# Power.net
KiCad netlist of a schematic drawn in Altium Designer
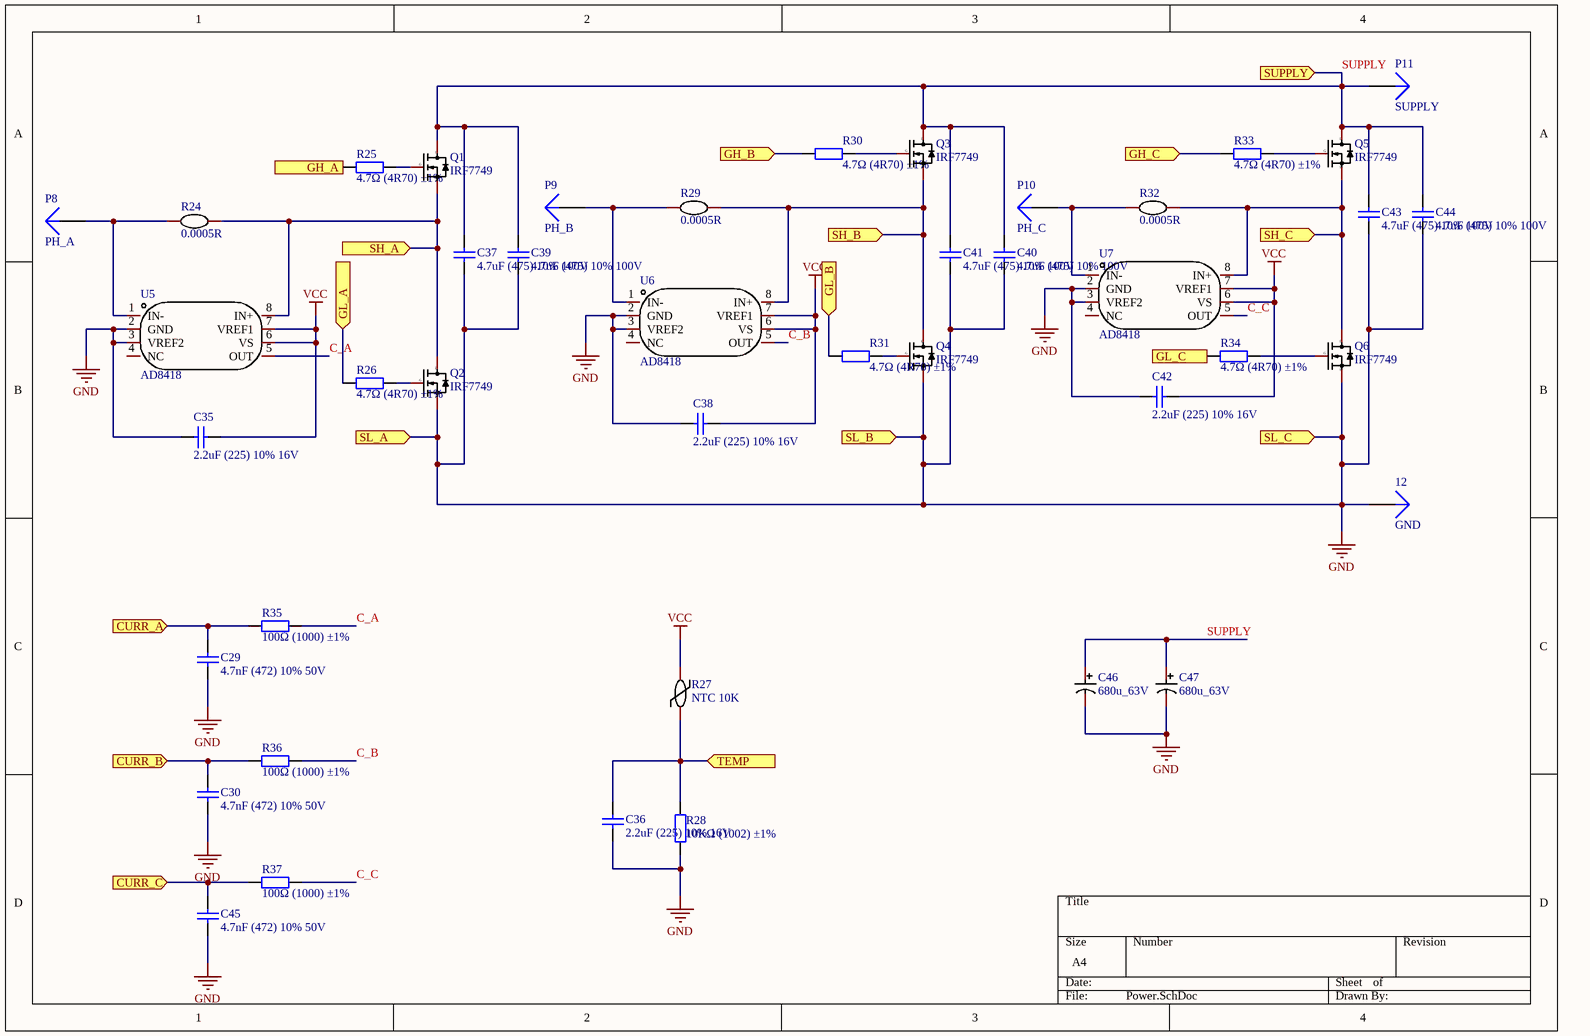
[diagram p0: Power.SchDoc]

(export (version "E")
  (design (tool "Eeschema 10.0.6"))
  (components
    (comp (ref "12")
      (value "GND")
      (footprint "Power PAD6x6")
      (description "Plug")
      (fields (field (name "PUBLISHER") "Altium Limited"))
      (libsource (lib "Miscellaneous Connectors") (part "Plug"))
    )
    (comp (ref "C29")
      (value "4.7nF (472) 10% 50V")
      (footprint "0603_C")
      (description "贴片电容")
      (libsource (lib "Miscellaneous Devices LC") (part "0603 4.7nF (472) 10% 50V"))
    )
    (comp (ref "C30")
      (value "4.7nF (472) 10% 50V")
      (footprint "0603_C")
      (description "贴片电容")
      (libsource (lib "Miscellaneous Devices LC") (part "0603 4.7nF (472) 10% 50V"))
    )
    (comp (ref "C35")
      (value "2.2uF (225) 10% 16V")
      (footprint "0603_C")
      (description "贴片电容")
      (libsource (lib "Miscellaneous Devices LC") (part "0603 2.2uF (225) 10% 16V"))
    )
    (comp (ref "C36")
      (value "2.2uF (225) 10% 16V")
      (footprint "0603_C")
      (description "贴片电容")
      (libsource (lib "Miscellaneous Devices LC") (part "0603 2.2uF (225) 10% 16V"))
    )
    (comp (ref "C37")
      (value "4.7uF (475) 10% 100V")
      (footprint "1210_C")
      (description "贴片电容")
      (libsource (lib "Miscellaneous Devices LC") (part "0603 4.7uF (475) 10% 16V"))
    )
    (comp (ref "C38")
      (value "2.2uF (225) 10% 16V")
      (footprint "0603_C")
      (description "贴片电容")
      (libsource (lib "Miscellaneous Devices LC") (part "0603 2.2uF (225) 10% 16V"))
    )
    (comp (ref "C39")
      (value "4.7uF (475) 10% 100V")
      (footprint "1210_C")
      (description "贴片电容")
      (libsource (lib "Miscellaneous Devices LC") (part "0603 4.7uF (475) 10% 16V"))
    )
    (comp (ref "C40")
      (value "4.7uF (475) 10% 100V")
      (footprint "1210_C")
      (description "贴片电容")
      (libsource (lib "Miscellaneous Devices LC") (part "0603 4.7uF (475) 10% 16V"))
    )
    (comp (ref "C41")
      (value "4.7uF (475) 10% 100V")
      (footprint "1210_C")
      (description "贴片电容")
      (libsource (lib "Miscellaneous Devices LC") (part "0603 4.7uF (475) 10% 16V"))
    )
    (comp (ref "C42")
      (value "2.2uF (225) 10% 16V")
      (footprint "0603_C")
      (description "贴片电容")
      (libsource (lib "Miscellaneous Devices LC") (part "0603 2.2uF (225) 10% 16V"))
    )
    (comp (ref "C43")
      (value "4.7uF (475) 10% 100V")
      (footprint "1210_C")
      (description "贴片电容")
      (libsource (lib "Miscellaneous Devices LC") (part "0603 4.7uF (475) 10% 16V"))
    )
    (comp (ref "C44")
      (value "4.7uF (475) 10% 100V")
      (footprint "1210_C")
      (description "贴片电容")
      (libsource (lib "Miscellaneous Devices LC") (part "0603 4.7uF (475) 10% 16V"))
    )
    (comp (ref "C45")
      (value "4.7nF (472) 10% 50V")
      (footprint "0603_C")
      (description "贴片电容")
      (libsource (lib "Miscellaneous Devices LC") (part "0603 4.7nF (472) 10% 50V"))
    )
    (comp (ref "C46") (value "680u_63V") (footprint "680u_63V") (libsource (lib "VESC_6") (part "680u_63V")))
    (comp (ref "C47") (value "680u_63V") (footprint "680u_63V") (libsource (lib "VESC_6") (part "680u_63V")))
    (comp (ref "P8")
      (value "PH_A")
      (footprint "POWER PAD")
      (description "Plug")
      (fields (field (name "PUBLISHER") "Altium Limited"))
      (libsource (lib "Miscellaneous Connectors") (part "Plug"))
    )
    (comp (ref "P9")
      (value "PH_B")
      (footprint "POWER PAD")
      (description "Plug")
      (fields (field (name "PUBLISHER") "Altium Limited"))
      (libsource (lib "Miscellaneous Connectors") (part "Plug"))
    )
    (comp (ref "P10")
      (value "PH_C")
      (footprint "POWER PAD")
      (description "Plug")
      (fields (field (name "PUBLISHER") "Altium Limited"))
      (libsource (lib "Miscellaneous Connectors") (part "Plug"))
    )
    (comp (ref "P11")
      (value "SUPPLY")
      (footprint "Power PAD6x6")
      (description "Plug")
      (fields (field (name "PUBLISHER") "Altium Limited"))
      (libsource (lib "Miscellaneous Connectors") (part "Plug"))
    )
    (comp (ref "Q1") (value "IRF7749") (footprint "IRF7749") (libsource (lib "VESC_6") (part "IRF7749")))
    (comp (ref "Q2") (value "IRF7749") (footprint "IRF7749") (libsource (lib "VESC_6") (part "IRF7749")))
    (comp (ref "Q3") (value "IRF7749") (footprint "IRF7749") (libsource (lib "VESC_6") (part "IRF7749")))
    (comp (ref "Q4") (value "IRF7749") (footprint "IRF7749") (libsource (lib "VESC_6") (part "IRF7749")))
    (comp (ref "Q5") (value "IRF7749") (footprint "IRF7749") (libsource (lib "VESC_6") (part "IRF7749")))
    (comp (ref "Q6") (value "IRF7749") (footprint "IRF7749") (libsource (lib "VESC_6") (part "IRF7749")))
    (comp (ref "R24") (value "0.0005R") (footprint "0.0005R") (libsource (lib "VESC_6") (part "0.0005R")))
    (comp (ref "R25")
      (value "4.7Ω (4R70) ±1%")
      (footprint "0603_R")
      (description "贴片电阻")
      (libsource (lib "Miscellaneous Devices LC") (part "0603 4.7Ω (4R70) 1%"))
    )
    (comp (ref "R26")
      (value "4.7Ω (4R70) ±1%")
      (footprint "0603_R")
      (description "贴片电阻")
      (libsource (lib "Miscellaneous Devices LC") (part "0603 4.7Ω (4R70) 1%"))
    )
    (comp (ref "R27") (value "NTC 10K") (footprint "NTC 10K") (libsource (lib "VESC_6") (part "NTC 10K")))
    (comp (ref "R28")
      (value "10KΩ (1002) ±1%")
      (footprint "0603_R")
      (description "贴片电阻")
      (libsource (lib "Miscellaneous Devices LC") (part "0603 10KΩ (1002) 1%"))
    )
    (comp (ref "R29") (value "0.0005R") (footprint "0.0005R") (libsource (lib "VESC_6") (part "0.0005R")))
    (comp (ref "R30")
      (value "4.7Ω (4R70) ±1%")
      (footprint "0603_R")
      (description "贴片电阻")
      (libsource (lib "Miscellaneous Devices LC") (part "0603 4.7Ω (4R70) 1%"))
    )
    (comp (ref "R31")
      (value "4.7Ω (4R70) ±1%")
      (footprint "0603_R")
      (description "贴片电阻")
      (libsource (lib "Miscellaneous Devices LC") (part "0603 4.7Ω (4R70) 1%"))
    )
    (comp (ref "R32") (value "0.0005R") (footprint "0.0005R") (libsource (lib "VESC_6") (part "0.0005R")))
    (comp (ref "R33")
      (value "4.7Ω (4R70) ±1%")
      (footprint "0603_R")
      (description "贴片电阻")
      (libsource (lib "Miscellaneous Devices LC") (part "0603 4.7Ω (4R70) 1%"))
    )
    (comp (ref "R34")
      (value "4.7Ω (4R70) ±1%")
      (footprint "0603_R")
      (description "贴片电阻")
      (libsource (lib "Miscellaneous Devices LC") (part "0603 4.7Ω (4R70) 1%"))
    )
    (comp (ref "R35")
      (value "100Ω (1000) ±1%")
      (footprint "0603_R")
      (description "贴片电阻")
      (libsource (lib "Miscellaneous Devices LC") (part "0603 100Ω (1000) 1%"))
    )
    (comp (ref "R36")
      (value "100Ω (1000) ±1%")
      (footprint "0603_R")
      (description "贴片电阻")
      (libsource (lib "Miscellaneous Devices LC") (part "0603 100Ω (1000) 1%"))
    )
    (comp (ref "R37")
      (value "100Ω (1000) ±1%")
      (footprint "0603_R")
      (description "贴片电阻")
      (libsource (lib "Miscellaneous Devices LC") (part "0603 100Ω (1000) 1%"))
    )
    (comp (ref "U5") (value "AD8418") (footprint "AD8418") (libsource (lib "VESC_6") (part "AD8418")))
    (comp (ref "U6") (value "AD8418") (footprint "AD8418") (libsource (lib "VESC_6") (part "AD8418")))
    (comp (ref "U7") (value "AD8418") (footprint "AD8418") (libsource (lib "VESC_6") (part "AD8418")))
  )
  (nets
    (net (code "1") (name "/CURR_A") (class "Default")
      (node (ref "C29") (pin "2") (pinfunction "2_2") (pintype "passive"))
      (node (ref "R35") (pin "1") (pinfunction "1_1") (pintype "passive"))
    )
    (net (code "2") (name "/CURR_B") (class "Default")
      (node (ref "C30") (pin "2") (pinfunction "2_2") (pintype "passive"))
      (node (ref "R36") (pin "1") (pinfunction "1_1") (pintype "passive"))
    )
    (net (code "3") (name "/CURR_C") (class "Default")
      (node (ref "C45") (pin "2") (pinfunction "2_2") (pintype "passive"))
      (node (ref "R37") (pin "1") (pinfunction "1_1") (pintype "passive"))
    )
    (net (code "4") (name "/C_A") (class "Default")
      (node (ref "R35") (pin "2") (pinfunction "2_2") (pintype "passive"))
      (node (ref "U5") (pin "5") (pinfunction "OUT_5") (pintype "passive"))
    )
    (net (code "5") (name "/C_B") (class "Default")
      (node (ref "R36") (pin "2") (pinfunction "2_2") (pintype "passive"))
      (node (ref "U6") (pin "5") (pinfunction "OUT_5") (pintype "passive"))
    )
    (net (code "6") (name "/C_C") (class "Default")
      (node (ref "R37") (pin "2") (pinfunction "2_2") (pintype "passive"))
      (node (ref "U7") (pin "5") (pinfunction "OUT_5") (pintype "passive"))
    )
    (net (code "7") (name "/GH_A") (class "Default")
      (node (ref "R25") (pin "1") (pinfunction "1_1") (pintype "passive"))
    )
    (net (code "8") (name "/GH_B") (class "Default")
      (node (ref "R30") (pin "1") (pinfunction "1_1") (pintype "passive"))
    )
    (net (code "9") (name "/GH_C") (class "Default")
      (node (ref "R33") (pin "1") (pinfunction "1_1") (pintype "passive"))
    )
    (net (code "10") (name "/GL_A") (class "Default")
      (node (ref "R26") (pin "1") (pinfunction "1_1") (pintype "passive"))
    )
    (net (code "11") (name "/GL_B") (class "Default")
      (node (ref "R31") (pin "1") (pinfunction "1_1") (pintype "passive"))
    )
    (net (code "12") (name "/GL_C") (class "Default")
      (node (ref "R34") (pin "1") (pinfunction "1_1") (pintype "passive"))
    )
    (net (code "13") (name "/SH_A") (class "Default")
      (node (ref "Q1") (pin "3") (pinfunction "S_3") (pintype "passive"))
      (node (ref "Q2") (pin "4") (pinfunction "D_4") (pintype "passive"))
      (node (ref "R24") (pin "2") (pinfunction "2_2") (pintype "passive"))
      (node (ref "U5") (pin "8") (pinfunction "IN+_8") (pintype "passive"))
    )
    (net (code "14") (name "/SH_B") (class "Default")
      (node (ref "Q3") (pin "3") (pinfunction "S_3") (pintype "passive"))
      (node (ref "Q4") (pin "4") (pinfunction "D_4") (pintype "passive"))
      (node (ref "R29") (pin "2") (pinfunction "2_2") (pintype "passive"))
      (node (ref "U6") (pin "8") (pinfunction "IN+_8") (pintype "passive"))
    )
    (net (code "15") (name "/SH_C") (class "Default")
      (node (ref "Q5") (pin "3") (pinfunction "S_3") (pintype "passive"))
      (node (ref "Q6") (pin "4") (pinfunction "D_4") (pintype "passive"))
      (node (ref "R32") (pin "2") (pinfunction "2_2") (pintype "passive"))
      (node (ref "U7") (pin "8") (pinfunction "IN+_8") (pintype "passive"))
    )
    (net (code "16") (name "/SUPPLY") (class "Default")
      (node (ref "C37") (pin "2") (pinfunction "2_2") (pintype "passive"))
      (node (ref "C39") (pin "2") (pinfunction "2_2") (pintype "passive"))
      (node (ref "C40") (pin "2") (pinfunction "2_2") (pintype "passive"))
      (node (ref "C41") (pin "2") (pinfunction "2_2") (pintype "passive"))
      (node (ref "C43") (pin "2") (pinfunction "2_2") (pintype "passive"))
      (node (ref "C44") (pin "2") (pinfunction "2_2") (pintype "passive"))
      (node (ref "C46") (pin "1") (pinfunction "1_1") (pintype "passive"))
      (node (ref "C47") (pin "1") (pinfunction "1_1") (pintype "passive"))
      (node (ref "P11") (pin "1") (pinfunction "1_1") (pintype "passive"))
      (node (ref "Q1") (pin "4") (pinfunction "D_4") (pintype "passive"))
      (node (ref "Q3") (pin "4") (pinfunction "D_4") (pintype "passive"))
      (node (ref "Q5") (pin "4") (pinfunction "D_4") (pintype "passive"))
    )
    (net (code "17") (name "/TEMP") (class "Default")
      (node (ref "C36") (pin "2") (pinfunction "2_2") (pintype "passive"))
      (node (ref "R27") (pin "1") (pinfunction "1_1") (pintype "passive"))
      (node (ref "R28") (pin "2") (pinfunction "2_2") (pintype "passive"))
    )
    (net (code "18") (name "GND") (class "Default")
      (node (ref "12") (pin "1") (pinfunction "1_1") (pintype "passive"))
      (node (ref "C29") (pin "1") (pinfunction "1_1") (pintype "passive"))
      (node (ref "C30") (pin "1") (pinfunction "1_1") (pintype "passive"))
      (node (ref "C35") (pin "1") (pinfunction "1_1") (pintype "passive"))
      (node (ref "C36") (pin "1") (pinfunction "1_1") (pintype "passive"))
      (node (ref "C37") (pin "1") (pinfunction "1_1") (pintype "passive"))
      (node (ref "C38") (pin "1") (pinfunction "1_1") (pintype "passive"))
      (node (ref "C39") (pin "1") (pinfunction "1_1") (pintype "passive"))
      (node (ref "C40") (pin "1") (pinfunction "1_1") (pintype "passive"))
      (node (ref "C41") (pin "1") (pinfunction "1_1") (pintype "passive"))
      (node (ref "C42") (pin "1") (pinfunction "1_1") (pintype "passive"))
      (node (ref "C43") (pin "1") (pinfunction "1_1") (pintype "passive"))
      (node (ref "C44") (pin "1") (pinfunction "1_1") (pintype "passive"))
      (node (ref "C45") (pin "1") (pinfunction "1_1") (pintype "passive"))
      (node (ref "C46") (pin "2") (pinfunction "2_2") (pintype "passive"))
      (node (ref "C47") (pin "2") (pinfunction "2_2") (pintype "passive"))
      (node (ref "Q2") (pin "3") (pinfunction "S_3") (pintype "passive"))
      (node (ref "Q4") (pin "3") (pinfunction "S_3") (pintype "passive"))
      (node (ref "Q6") (pin "3") (pinfunction "S_3") (pintype "passive"))
      (node (ref "R28") (pin "1") (pinfunction "1_1") (pintype "passive"))
      (node (ref "U5") (pin "2") (pinfunction "GND_2") (pintype "passive"))
      (node (ref "U5") (pin "3") (pinfunction "VREF2_3") (pintype "passive"))
      (node (ref "U6") (pin "2") (pinfunction "GND_2") (pintype "passive"))
      (node (ref "U6") (pin "3") (pinfunction "VREF2_3") (pintype "passive"))
      (node (ref "U7") (pin "2") (pinfunction "GND_2") (pintype "passive"))
      (node (ref "U7") (pin "3") (pinfunction "VREF2_3") (pintype "passive"))
    )
    (net (code "19") (name "Net-(Q1-G)") (class "Default")
      (node (ref "Q1") (pin "1") (pinfunction "G_1") (pintype "passive"))
      (node (ref "R25") (pin "2") (pinfunction "2_2") (pintype "passive"))
    )
    (net (code "20") (name "Net-(Q2-G)") (class "Default")
      (node (ref "Q2") (pin "1") (pinfunction "G_1") (pintype "passive"))
      (node (ref "R26") (pin "2") (pinfunction "2_2") (pintype "passive"))
    )
    (net (code "21") (name "Net-(Q3-G)") (class "Default")
      (node (ref "Q3") (pin "1") (pinfunction "G_1") (pintype "passive"))
      (node (ref "R30") (pin "2") (pinfunction "2_2") (pintype "passive"))
    )
    (net (code "22") (name "Net-(Q4-G)") (class "Default")
      (node (ref "Q4") (pin "1") (pinfunction "G_1") (pintype "passive"))
      (node (ref "R31") (pin "2") (pinfunction "2_2") (pintype "passive"))
    )
    (net (code "23") (name "Net-(Q5-G)") (class "Default")
      (node (ref "Q5") (pin "1") (pinfunction "G_1") (pintype "passive"))
      (node (ref "R33") (pin "2") (pinfunction "2_2") (pintype "passive"))
    )
    (net (code "24") (name "Net-(Q6-G)") (class "Default")
      (node (ref "Q6") (pin "1") (pinfunction "G_1") (pintype "passive"))
      (node (ref "R34") (pin "2") (pinfunction "2_2") (pintype "passive"))
    )
    (net (code "25") (name "Net-(U5-IN-)") (class "Default")
      (node (ref "P8") (pin "1") (pinfunction "1_1") (pintype "passive"))
      (node (ref "R24") (pin "1") (pinfunction "1_1") (pintype "passive"))
      (node (ref "U5") (pin "1") (pinfunction "IN-_1") (pintype "passive"))
    )
    (net (code "26") (name "Net-(U6-IN-)") (class "Default")
      (node (ref "P9") (pin "1") (pinfunction "1_1") (pintype "passive"))
      (node (ref "R29") (pin "1") (pinfunction "1_1") (pintype "passive"))
      (node (ref "U6") (pin "1") (pinfunction "IN-_1") (pintype "passive"))
    )
    (net (code "27") (name "Net-(U7-IN-)") (class "Default")
      (node (ref "P10") (pin "1") (pinfunction "1_1") (pintype "passive"))
      (node (ref "R32") (pin "1") (pinfunction "1_1") (pintype "passive"))
      (node (ref "U7") (pin "1") (pinfunction "IN-_1") (pintype "passive"))
    )
    (net (code "28") (name "VCC") (class "Default")
      (node (ref "C35") (pin "2") (pinfunction "2_2") (pintype "passive"))
      (node (ref "C38") (pin "2") (pinfunction "2_2") (pintype "passive"))
      (node (ref "C42") (pin "2") (pinfunction "2_2") (pintype "passive"))
      (node (ref "R27") (pin "2") (pinfunction "2_2") (pintype "passive"))
      (node (ref "U5") (pin "6") (pinfunction "VS_6") (pintype "passive"))
      (node (ref "U5") (pin "7") (pinfunction "VREF1_7") (pintype "passive"))
      (node (ref "U6") (pin "6") (pinfunction "VS_6") (pintype "passive"))
      (node (ref "U6") (pin "7") (pinfunction "VREF1_7") (pintype "passive"))
      (node (ref "U7") (pin "6") (pinfunction "VS_6") (pintype "passive"))
      (node (ref "U7") (pin "7") (pinfunction "VREF1_7") (pintype "passive"))
    )
    (net (code "29") (name "unconnected-(U5-NC-Pad4)") (class "Default")
      (node (ref "U5") (pin "4") (pinfunction "NC_4") (pintype "passive"))
    )
    (net (code "30") (name "unconnected-(U6-NC-Pad4)") (class "Default")
      (node (ref "U6") (pin "4") (pinfunction "NC_4") (pintype "passive"))
    )
    (net (code "31") (name "unconnected-(U7-NC-Pad4)") (class "Default")
      (node (ref "U7") (pin "4") (pinfunction "NC_4") (pintype "passive"))
    )
  )
)
